# Accelerometer.net
KiCad netlist of a schematic drawn in Altium Designer
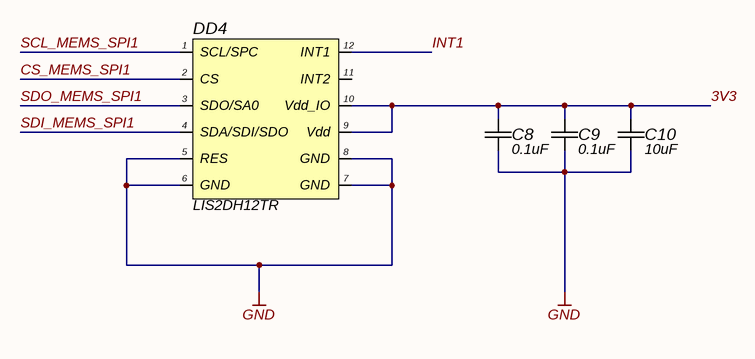
[diagram p0: Accelerometer.SchDoc]

(export (version "E")
  (design (tool "Eeschema 10.0.6"))
  (components
    (comp (ref "C8")
      (value "0.1uF")
      (footprint "CAP: 0603")
      (fields
        (field (name "MANUFACTURER") "Yageo")
        (field (name "PARTNUMBER") "CC0603KRX7R7BB104")
        (field (name "VALUEMANUFACTURERPARTNUMBER") "Ceramic capacitor, 0.1uF, X7R, ±10%, 16V, 0603, -55...+125°C")
      )
      (libsource (lib "capacitor") (part "Ceramic_0603"))
    )
    (comp (ref "C9")
      (value "0.1uF")
      (footprint "CAP: 0603")
      (fields
        (field (name "MANUFACTURER") "Yageo")
        (field (name "PARTNUMBER") "CC0603KRX7R7BB104")
        (field (name "VALUEMANUFACTURERPARTNUMBER") "Ceramic capacitor, 0.1uF, X7R, ±10%, 16V, 0603, -55...+125°C")
      )
      (libsource (lib "capacitor") (part "Ceramic_0603"))
    )
    (comp (ref "C10")
      (value "10uF")
      (footprint "CAP: 0603")
      (fields
        (field (name "MANUFACTURER") "Yageo")
        (field (name "PARTNUMBER") "CC0603KRX7R7BB104")
        (field (name "VALUEMANUFACTURERPARTNUMBER") "Ceramic capacitor, 10uF, X7R, ±10%, 16V, 0603, -55...+125°C")
      )
      (libsource (lib "capacitor") (part "Ceramic_0603"))
    )
    (comp (ref "DD4")
      (value "LIS2DH12TR")
      (footprint "12-LGA")
      (description "MEMS accelerometer")
      (libsource (lib "electromechanics") (part "LIS2DH12TR"))
    )
  )
  (nets
    (net (code "1") (name "/3V3") (class "Default")
      (node (ref "C10") (pin "2") (pinfunction "2_2") (pintype "passive"))
      (node (ref "C8") (pin "2") (pinfunction "2_2") (pintype "passive"))
      (node (ref "C9") (pin "2") (pinfunction "2_2") (pintype "passive"))
      (node (ref "DD4") (pin "10") (pinfunction "Vdd_IO_10") (pintype "passive"))
      (node (ref "DD4") (pin "9") (pinfunction "Vdd_9") (pintype "passive"))
    )
    (net (code "2") (name "/CS_MEMS_SPI1") (class "Default")
      (node (ref "DD4") (pin "2") (pinfunction "CS_2") (pintype "passive"))
    )
    (net (code "3") (name "/INT1") (class "Default")
      (node (ref "DD4") (pin "12") (pinfunction "INT1_12") (pintype "passive"))
    )
    (net (code "4") (name "/SCL_MEMS_SPI1") (class "Default")
      (node (ref "DD4") (pin "1") (pinfunction "SCL/SPC_1") (pintype "passive"))
    )
    (net (code "5") (name "/SDI_MEMS_SPI1") (class "Default")
      (node (ref "DD4") (pin "4") (pinfunction "SDA/SDI/SDO_4") (pintype "passive"))
    )
    (net (code "6") (name "/SDO_MEMS_SPI1") (class "Default")
      (node (ref "DD4") (pin "3") (pinfunction "SDO/SA0_3") (pintype "passive"))
    )
    (net (code "7") (name "GND") (class "Default")
      (node (ref "C10") (pin "1") (pinfunction "1_1") (pintype "passive"))
      (node (ref "C8") (pin "1") (pinfunction "1_1") (pintype "passive"))
      (node (ref "C9") (pin "1") (pinfunction "1_1") (pintype "passive"))
      (node (ref "DD4") (pin "5") (pinfunction "RES_5") (pintype "passive"))
      (node (ref "DD4") (pin "6") (pinfunction "GND_6") (pintype "passive"))
      (node (ref "DD4") (pin "7") (pinfunction "GND_7") (pintype "passive"))
      (node (ref "DD4") (pin "8") (pinfunction "GND_8") (pintype "passive"))
    )
    (net (code "8") (name "unconnected-(DD4-INT2-Pad11)") (class "Default")
      (node (ref "DD4") (pin "11") (pinfunction "INT2_11") (pintype "passive"))
    )
  )
)
